# Final_try_I_hope.net
KiCad netlist of a schematic drawn in EAGLE
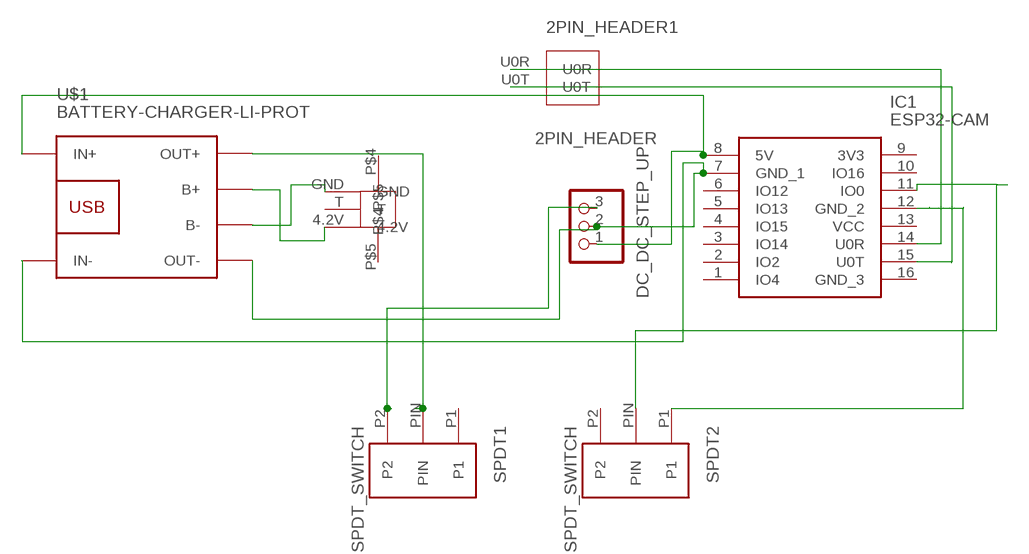
[diagram p0: schematic, sheet 1]

(export (version "E")
  (design (tool "Eeschema 10.0.6"))
  (components
    (comp (ref "2PIN_HEADER1")
      (value "2PIN_HEADER")
      (footprint "eagle-import:2PIN_HEADER")
      (libsource (lib "eagle-import") (part "2PIN_HEADER"))
    )
    (comp (ref "DC_DC_STEP_UP")
      (value "PINHD-1X3")
      (footprint "eagle-import:1X03")
      (libsource (lib "eagle-import") (part "PINHD-1X3"))
    )
    (comp (ref "IC1")
      (value "ESP32-CAM")
      (footprint "eagle-import:ESP32CAM")
      (libsource (lib "eagle-import") (part "ESP32-CAM"))
    )
    (comp (ref "SPDT1")
      (value "SPDT_SWITCH")
      (footprint "eagle-import:SPDT_SWITCH")
      (libsource (lib "eagle-import") (part "SPDT_SWITCH"))
    )
    (comp (ref "SPDT2")
      (value "SPDT_SWITCH")
      (footprint "eagle-import:SPDT_SWITCH")
      (libsource (lib "eagle-import") (part "SPDT_SWITCH"))
    )
    (comp (ref "U$1")
      (value "BATTERY-CHARGER-LI-PROT")
      (footprint "eagle-import:BATTERY-CHARGER-LI-PROT")
      (libsource (lib "eagle-import") (part "BATTERY-CHARGER-LI-PROT"))
    )
    (comp (ref "U$2")
      (value "BATTERY_CONNECTOR")
      (footprint "eagle-import:BATTERY_CONNECTOR")
      (libsource (lib "eagle-import") (part "BATTERY_CONNECTOR"))
    )
  )
  (nets
    (net (code "1") (name "Net-(DC_DC_STEP_UP-Pad3)") (class "Default")
      (node (ref "DC_DC_STEP_UP") (pin "3") (pinfunction "3_3") (pintype "passive"))
      (node (ref "SPDT1") (pin "P2") (pinfunction "P2_P2") (pintype "bidirectional"))
    )
    (net (code "2") (name "Net-(IC1-5V)") (class "Default")
      (node (ref "DC_DC_STEP_UP") (pin "1") (pinfunction "1_1") (pintype "passive"))
      (node (ref "IC1") (pin "8") (pinfunction "5V_8") (pintype "bidirectional"))
      (node (ref "U$1") (pin "IN+") (pinfunction "IN+_IN+") (pintype "bidirectional"))
    )
    (net (code "3") (name "Net-(IC1-GND_1)") (class "Default")
      (node (ref "DC_DC_STEP_UP") (pin "2") (pinfunction "2_2") (pintype "passive"))
      (node (ref "IC1") (pin "7") (pinfunction "GND_1_7") (pintype "bidirectional"))
      (node (ref "U$1") (pin "IN-") (pinfunction "IN-_IN-") (pintype "bidirectional"))
      (node (ref "U$1") (pin "OUT-") (pinfunction "OUT-_OUT-") (pintype "bidirectional"))
    )
    (net (code "4") (name "Net-(IC1-GND_2)") (class "Default")
      (node (ref "IC1") (pin "12") (pinfunction "GND_2_12") (pintype "bidirectional"))
      (node (ref "SPDT2") (pin "P1") (pinfunction "P1_P1") (pintype "bidirectional"))
    )
    (net (code "5") (name "Net-(IC1-IO0)") (class "Default")
      (node (ref "IC1") (pin "11") (pinfunction "IO0_11") (pintype "bidirectional"))
      (node (ref "SPDT2") (pin "PIN") (pinfunction "PIN_PIN") (pintype "bidirectional"))
    )
    (net (code "6") (name "Net-(IC1-U0R)") (class "Default")
      (node (ref "2PIN_HEADER1") (pin "U0R") (pinfunction "U0R_U0R") (pintype "bidirectional"))
      (node (ref "IC1") (pin "14") (pinfunction "U0R_14") (pintype "bidirectional"))
    )
    (net (code "7") (name "Net-(IC1-U0T)") (class "Default")
      (node (ref "2PIN_HEADER1") (pin "U0T") (pinfunction "U0T_U0T") (pintype "bidirectional"))
      (node (ref "IC1") (pin "15") (pinfunction "U0T_15") (pintype "bidirectional"))
    )
    (net (code "8") (name "Net-(SPDT1-PadPIN)") (class "Default")
      (node (ref "SPDT1") (pin "PIN") (pinfunction "PIN_PIN") (pintype "bidirectional"))
      (node (ref "U$1") (pin "OUT+") (pinfunction "OUT+_OUT+") (pintype "bidirectional"))
    )
    (net (code "9") (name "Net-(U$1-PadB+)") (class "Default")
      (node (ref "U$1") (pin "B+") (pinfunction "B+_B+") (pintype "bidirectional"))
      (node (ref "U$2") (pin "4.2V") (pinfunction "4.2V_4.2V") (pintype "bidirectional"))
    )
    (net (code "10") (name "Net-(U$1-PadB-)") (class "Default")
      (node (ref "U$1") (pin "B-") (pinfunction "B-_B-") (pintype "bidirectional"))
      (node (ref "U$2") (pin "GND") (pinfunction "GND_GND") (pintype "bidirectional"))
    )
    (net (code "11") (name "unconnected-(IC1-3V3-Pad9)") (class "Default")
      (node (ref "IC1") (pin "9") (pinfunction "3V3_9") (pintype "bidirectional"))
    )
    (net (code "12") (name "unconnected-(IC1-GND_3-Pad16)") (class "Default")
      (node (ref "IC1") (pin "16") (pinfunction "GND_3_16") (pintype "bidirectional"))
    )
    (net (code "13") (name "unconnected-(IC1-IO2-Pad2)") (class "Default")
      (node (ref "IC1") (pin "2") (pinfunction "IO2_2") (pintype "bidirectional"))
    )
    (net (code "14") (name "unconnected-(IC1-IO4-Pad1)") (class "Default")
      (node (ref "IC1") (pin "1") (pinfunction "IO4_1") (pintype "bidirectional"))
    )
    (net (code "15") (name "unconnected-(IC1-IO12-Pad6)") (class "Default")
      (node (ref "IC1") (pin "6") (pinfunction "IO12_6") (pintype "bidirectional"))
    )
    (net (code "16") (name "unconnected-(IC1-IO13-Pad5)") (class "Default")
      (node (ref "IC1") (pin "5") (pinfunction "IO13_5") (pintype "bidirectional"))
    )
    (net (code "17") (name "unconnected-(IC1-IO14-Pad3)") (class "Default")
      (node (ref "IC1") (pin "3") (pinfunction "IO14_3") (pintype "bidirectional"))
    )
    (net (code "18") (name "unconnected-(IC1-IO15-Pad4)") (class "Default")
      (node (ref "IC1") (pin "4") (pinfunction "IO15_4") (pintype "bidirectional"))
    )
    (net (code "19") (name "unconnected-(IC1-IO16-Pad10)") (class "Default")
      (node (ref "IC1") (pin "10") (pinfunction "IO16_10") (pintype "bidirectional"))
    )
    (net (code "20") (name "unconnected-(IC1-VCC-Pad13)") (class "Default")
      (node (ref "IC1") (pin "13") (pinfunction "VCC_13") (pintype "bidirectional"))
    )
    (net (code "21") (name "unconnected-(SPDT1-PadP1)") (class "Default")
      (node (ref "SPDT1") (pin "P1") (pinfunction "P1_P1") (pintype "bidirectional"))
    )
    (net (code "22") (name "unconnected-(SPDT2-PadP2)") (class "Default")
      (node (ref "SPDT2") (pin "P2") (pinfunction "P2_P2") (pintype "bidirectional"))
    )
    (net (code "23") (name "unconnected-(U$2-PadP$4)") (class "Default")
      (node (ref "U$2") (pin "P$4") (pinfunction "P$4_P$4") (pintype "bidirectional"))
    )
    (net (code "24") (name "unconnected-(U$2-PadP$5)") (class "Default")
      (node (ref "U$2") (pin "P$5") (pinfunction "P$5_P$5") (pintype "bidirectional"))
    )
    (net (code "25") (name "unconnected-(U$2-PadT)") (class "Default")
      (node (ref "U$2") (pin "T") (pinfunction "T_T") (pintype "bidirectional"))
    )
  )
)
